# 01_ESP32_MAIN_A.net
KiCad netlist of a schematic drawn in Altium Designer
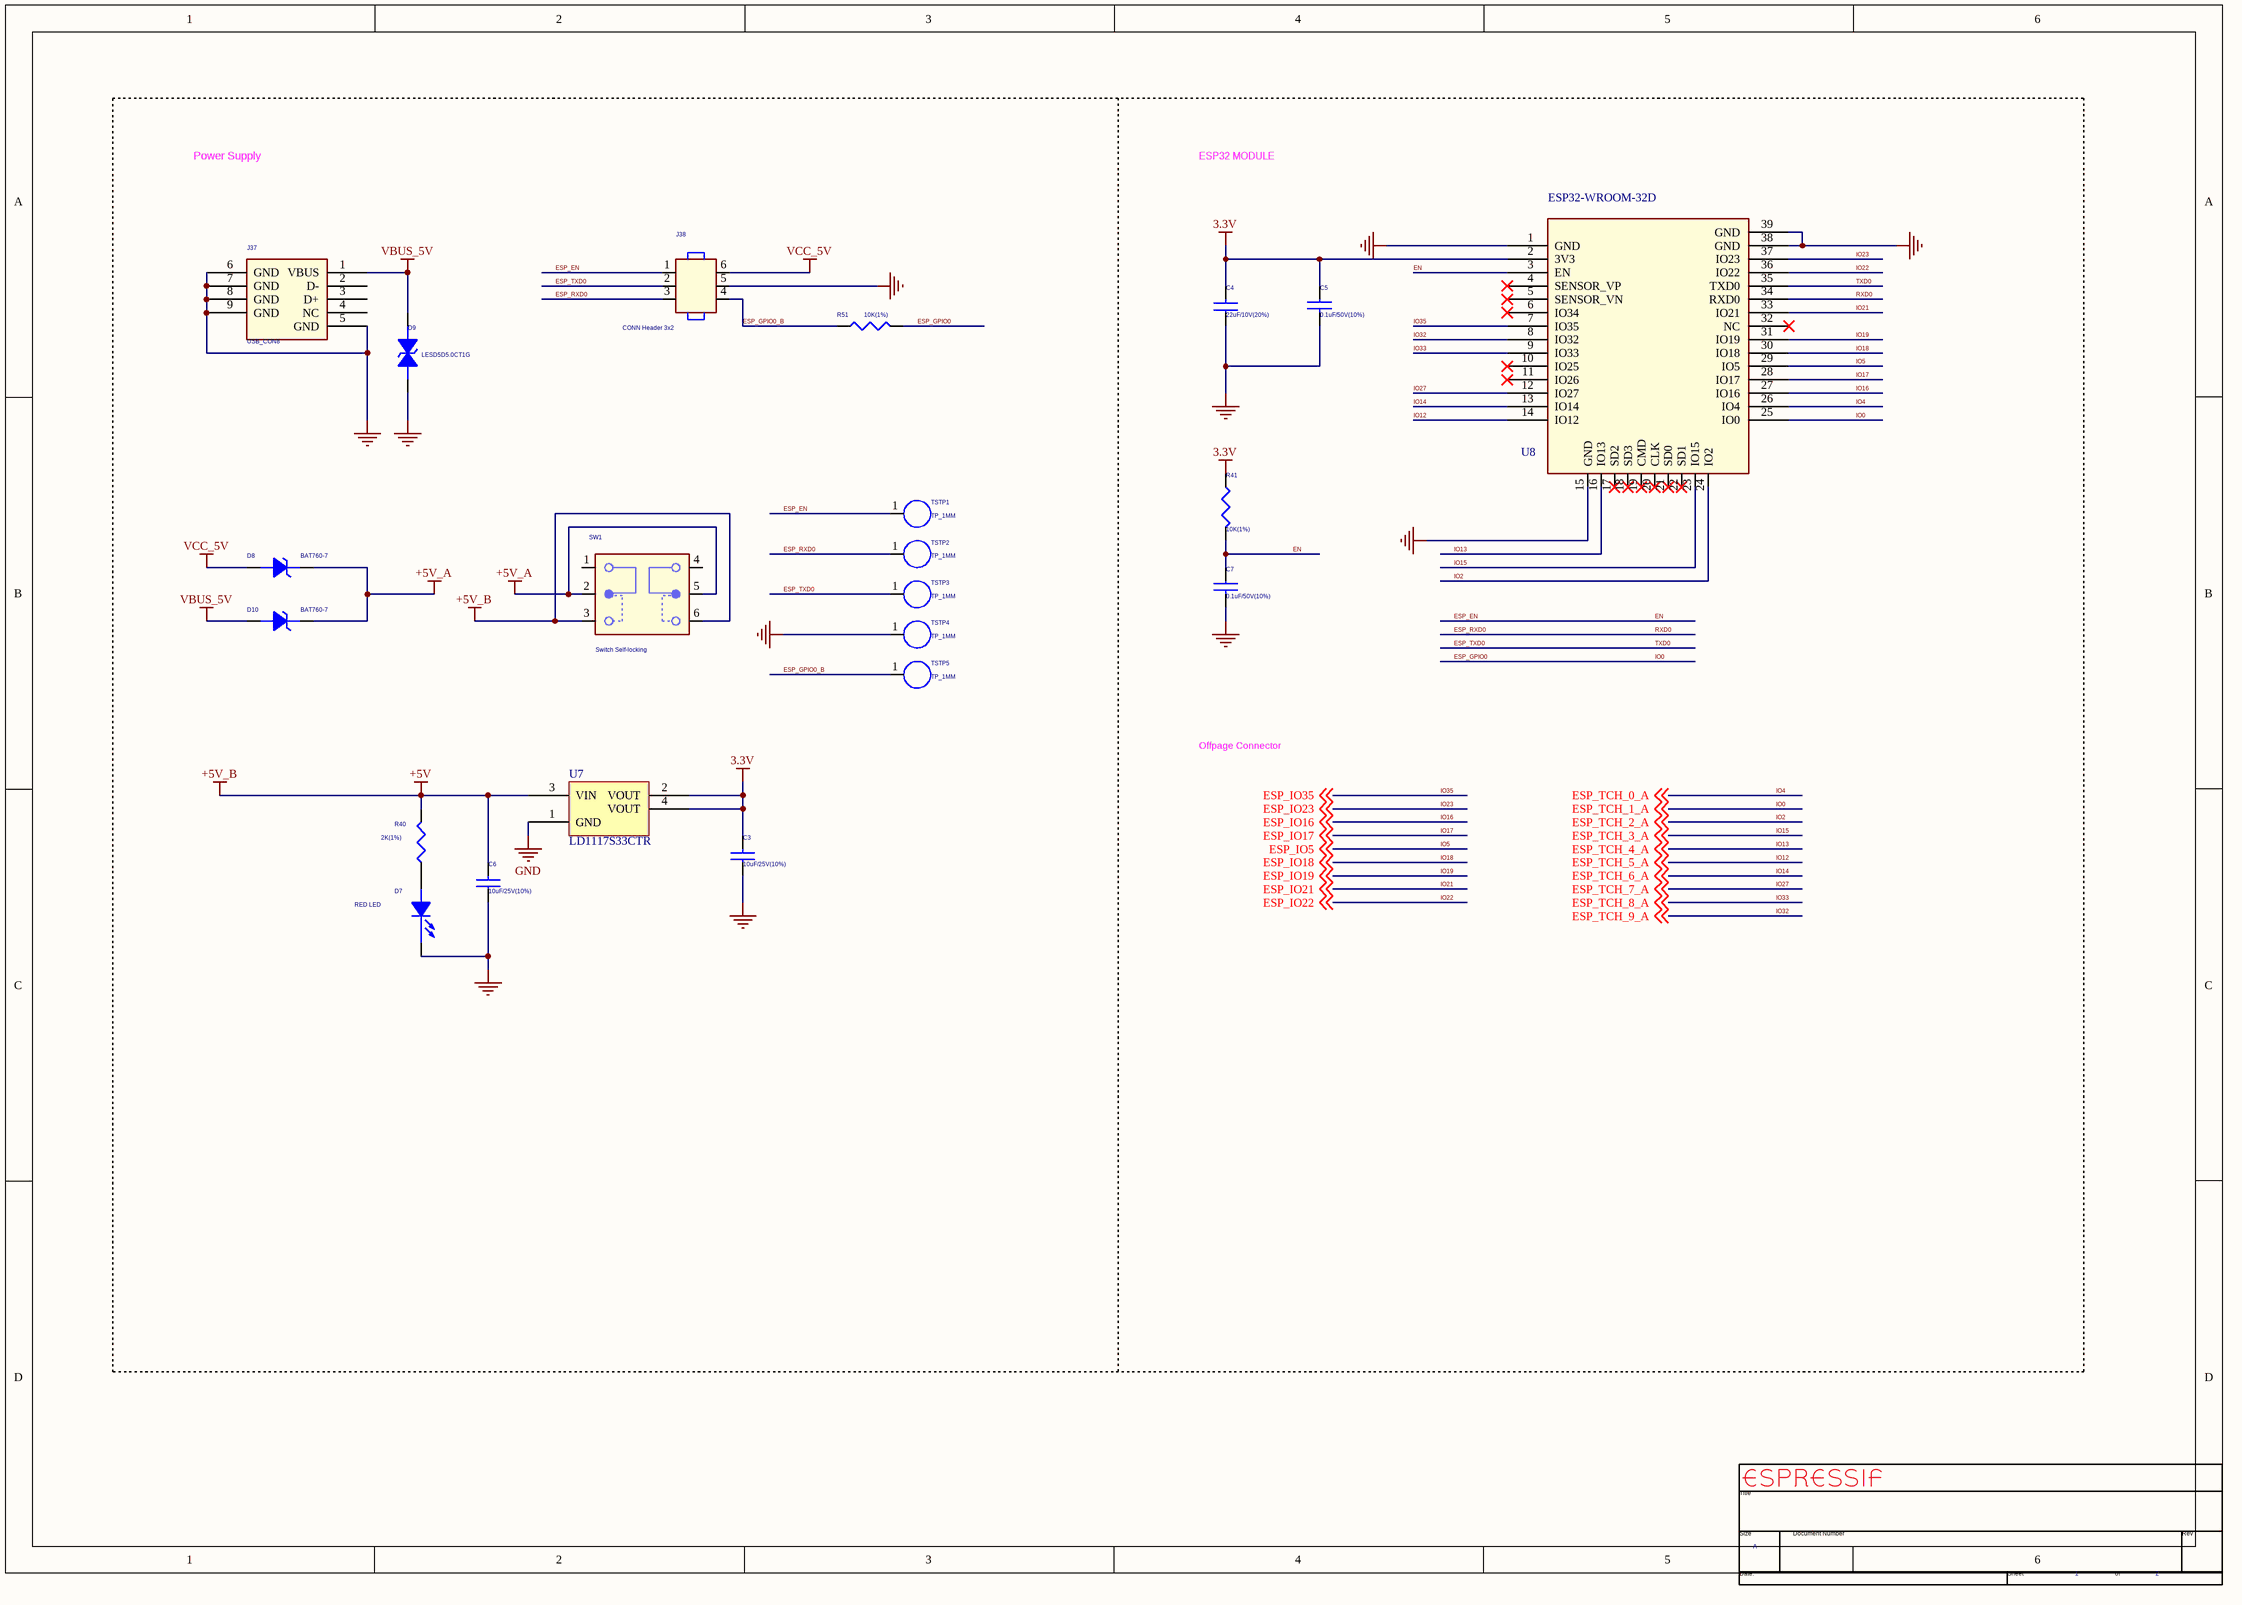
[diagram p0: 01 ESP32 MAIN_A.SchDoc]

(export (version "E")
  (design (tool "Eeschema 10.0.6"))
  (components
    (comp (ref "C3") (value "10uF/25V(10%)") (footprint "0603C") (libsource (lib "*") (part "CAP NP")))
    (comp (ref "C4") (value "22uF/10V(20%)") (footprint "C0603") (libsource (lib "*") (part "CAP NP")))
    (comp (ref "C5") (value "0.1uF/50V(10%)") (footprint "C0402") (libsource (lib "*") (part "CAP NP")))
    (comp (ref "C6") (value "10uF/25V(10%)") (footprint "0603C") (libsource (lib "*") (part "CAP NP")))
    (comp (ref "C7") (value "0.1uF/50V(10%)") (footprint "C0402") (libsource (lib "*") (part "CAP NP")))
    (comp (ref "D7") (value "RED LED") (footprint "0603D/A") (libsource (lib "*") (part "LED_1")))
    (comp (ref "D8") (value "BAT760-7") (footprint "SOD-323") (libsource (lib "*") (part "DIODE_POWER")))
    (comp (ref "D9")
      (value "LESD5D5.0CT1G")
      (footprint "ESD0402")
      (libsource (lib "*") (part "DIODE BI-DIR TRIG"))
    )
    (comp (ref "D10") (value "BAT760-7") (footprint "SOD-323") (libsource (lib "*") (part "DIODE_POWER")))
    (comp (ref "J37") (value "USB_CON8") (footprint "USB_5P") (libsource (lib "*") (part "CON4_2")))
    (comp (ref "J38")
      (value "CONN Header 3x2")
      (footprint "DC3-6P-1P27")
      (libsource (lib "*") (part "12 HEADER_9"))
    )
    (comp (ref "R40") (value "2K(1%)") (footprint "0402R") (libsource (lib "*") (part "RESISTOR_0")))
    (comp (ref "R41") (value "10K(1%)") (footprint "0402R") (libsource (lib "*") (part "RESISTOR_0")))
    (comp (ref "R51") (value "10K(1%)") (footprint "0402R") (libsource (lib "*") (part "RESISTOR_0")))
    (comp (ref "SW1")
      (value "Switch Self-locking")
      (footprint "SW5858-6")
      (libsource (lib "*") (part "Switch_selflocking_6p"))
    )
    (comp (ref "TSTP1") (value "TP_1MM") (footprint "TP_1MM") (libsource (lib "*") (part "CON1_0")))
    (comp (ref "TSTP2") (value "TP_1MM") (footprint "TP_1MM") (libsource (lib "*") (part "CON1_0")))
    (comp (ref "TSTP3") (value "TP_1MM") (footprint "TP_1MM") (libsource (lib "*") (part "CON1_0")))
    (comp (ref "TSTP4") (value "TP_1MM") (footprint "TP_1MM") (libsource (lib "*") (part "CON1_0")))
    (comp (ref "TSTP5") (value "TP_1MM") (footprint "TP_1MM") (libsource (lib "*") (part "CON1_0")))
    (comp (ref "U7")
      (value "LD1117S33CTR")
      (footprint "ST SOT-223")
      (description "IC REG LDO 3.3V 0.8A SOT223")
      (fields (field (name "MANUFACTURER") "STMicroelectronics"))
      (libsource (lib "Celestial Library Database") (part "ST LD1117"))
    )
    (comp (ref "U8")
      (value "ESP32-WROOM-32D")
      (footprint "*MODULE_ESP32-WROOM-32D")
      (description "IC: SoC; GPIO, I2C, I2S, IR, SD, SDIO, SPI, UART; 2.7Ã·3.6VDC; 20dBm")
      (fields (field (name "MF") "Espressif Systems"))
      (libsource (lib "ESP32-WROOM-32D") (part "ESP32-WROOM-32D"))
    )
  )
  (nets
    (net (code "1") (name "+5V") (class "Default")
      (node (ref "C6") (pin "2") (pinfunction "2_2") (pintype "passive"))
      (node (ref "R40") (pin "1") (pinfunction "1_1") (pintype "passive"))
      (node (ref "SW1") (pin "3") (pinfunction "NO1_3") (pintype "passive"))
      (node (ref "SW1") (pin "6") (pinfunction "NO2_6") (pintype "passive"))
      (node (ref "U7") (pin "3") (pinfunction "VIN_3") (pintype "passive"))
    )
    (net (code "2") (name "+5V_A") (class "Default")
      (node (ref "D10") (pin "1") (pinfunction "1_1") (pintype "passive"))
      (node (ref "D8") (pin "1") (pinfunction "1_1") (pintype "passive"))
      (node (ref "SW1") (pin "2") (pinfunction "COM1_2") (pintype "passive"))
      (node (ref "SW1") (pin "5") (pinfunction "COM2_5") (pintype "passive"))
    )
    (net (code "3") (name "/EN") (class "Default")
      (node (ref "C7") (pin "1") (pinfunction "1_1") (pintype "passive"))
      (node (ref "J38") (pin "1") (pinfunction "1_1") (pintype "passive"))
      (node (ref "R41") (pin "2") (pinfunction "2_2") (pintype "passive"))
      (node (ref "TSTP1") (pin "1") (pinfunction "1_1") (pintype "passive"))
      (node (ref "U8") (pin "3") (pinfunction "EN_3") (pintype "passive"))
    )
    (net (code "4") (name "/ESP_GPIO0_B") (class "Default")
      (node (ref "J38") (pin "4") (pinfunction "4_4") (pintype "passive"))
      (node (ref "R51") (pin "1") (pinfunction "1_1") (pintype "passive"))
      (node (ref "TSTP5") (pin "1") (pinfunction "1_1") (pintype "passive"))
    )
    (net (code "5") (name "/ESP_RXD0") (class "Default")
      (node (ref "J38") (pin "3") (pinfunction "3_3") (pintype "passive"))
      (node (ref "TSTP2") (pin "1") (pinfunction "1_1") (pintype "passive"))
      (node (ref "U8") (pin "34") (pinfunction "RXD0_34") (pintype "passive"))
    )
    (net (code "6") (name "/ESP_TXD0") (class "Default")
      (node (ref "J38") (pin "2") (pinfunction "2_2") (pintype "passive"))
      (node (ref "TSTP3") (pin "1") (pinfunction "1_1") (pintype "passive"))
      (node (ref "U8") (pin "35") (pinfunction "TXD0_35") (pintype "passive"))
    )
    (net (code "7") (name "3.3V") (class "Default")
      (node (ref "C3") (pin "2") (pinfunction "2_2") (pintype "passive"))
      (node (ref "C4") (pin "2") (pinfunction "2_2") (pintype "passive"))
      (node (ref "C5") (pin "1") (pinfunction "1_1") (pintype "passive"))
      (node (ref "R41") (pin "1") (pinfunction "1_1") (pintype "passive"))
      (node (ref "U7") (pin "2") (pinfunction "VOUT_2") (pintype "passive"))
      (node (ref "U7") (pin "4") (pinfunction "VOUT_4") (pintype "passive"))
      (node (ref "U8") (pin "2") (pinfunction "3V3_2") (pintype "power_in"))
    )
    (net (code "8") (name "ESP_IO5") (class "Default")
      (node (ref "U8") (pin "29") (pinfunction "IO5_29") (pintype "passive"))
    )
    (net (code "9") (name "ESP_IO16") (class "Default")
      (node (ref "U8") (pin "27") (pinfunction "IO16_27") (pintype "passive"))
    )
    (net (code "10") (name "ESP_IO17") (class "Default")
      (node (ref "U8") (pin "28") (pinfunction "IO17_28") (pintype "passive"))
    )
    (net (code "11") (name "ESP_IO18") (class "Default")
      (node (ref "U8") (pin "30") (pinfunction "IO18_30") (pintype "passive"))
    )
    (net (code "12") (name "ESP_IO19") (class "Default")
      (node (ref "U8") (pin "31") (pinfunction "IO19_31") (pintype "passive"))
    )
    (net (code "13") (name "ESP_IO21") (class "Default")
      (node (ref "U8") (pin "33") (pinfunction "IO21_33") (pintype "passive"))
    )
    (net (code "14") (name "ESP_IO22") (class "Default")
      (node (ref "U8") (pin "36") (pinfunction "IO22_36") (pintype "passive"))
    )
    (net (code "15") (name "ESP_IO23") (class "Default")
      (node (ref "U8") (pin "37") (pinfunction "IO23_37") (pintype "passive"))
    )
    (net (code "16") (name "ESP_IO35") (class "Default")
      (node (ref "U8") (pin "7") (pinfunction "IO35_7") (pintype "passive"))
    )
    (net (code "17") (name "ESP_TCH_0_A") (class "Default")
      (node (ref "U8") (pin "26") (pinfunction "IO4_26") (pintype "passive"))
    )
    (net (code "18") (name "ESP_TCH_1_A") (class "Default")
      (node (ref "R51") (pin "2") (pinfunction "2_2") (pintype "passive"))
      (node (ref "U8") (pin "25") (pinfunction "IO0_25") (pintype "passive"))
    )
    (net (code "19") (name "ESP_TCH_2_A") (class "Default")
      (node (ref "U8") (pin "24") (pinfunction "IO2_24") (pintype "passive"))
    )
    (net (code "20") (name "ESP_TCH_3_A") (class "Default")
      (node (ref "U8") (pin "23") (pinfunction "IO15_23") (pintype "passive"))
    )
    (net (code "21") (name "ESP_TCH_4_A") (class "Default")
      (node (ref "U8") (pin "16") (pinfunction "IO13_16") (pintype "passive"))
    )
    (net (code "22") (name "ESP_TCH_5_A") (class "Default")
      (node (ref "U8") (pin "14") (pinfunction "IO12_14") (pintype "passive"))
    )
    (net (code "23") (name "ESP_TCH_6_A") (class "Default")
      (node (ref "U8") (pin "13") (pinfunction "IO14_13") (pintype "passive"))
    )
    (net (code "24") (name "ESP_TCH_7_A") (class "Default")
      (node (ref "U8") (pin "12") (pinfunction "IO27_12") (pintype "passive"))
    )
    (net (code "25") (name "ESP_TCH_8_A") (class "Default")
      (node (ref "U8") (pin "9") (pinfunction "IO33_9") (pintype "passive"))
    )
    (net (code "26") (name "ESP_TCH_9_A") (class "Default")
      (node (ref "U8") (pin "8") (pinfunction "IO32_8") (pintype "passive"))
    )
    (net (code "27") (name "GND") (class "Default")
      (node (ref "C3") (pin "1") (pinfunction "1_1") (pintype "passive"))
      (node (ref "C4") (pin "1") (pinfunction "1_1") (pintype "passive"))
      (node (ref "C5") (pin "2") (pinfunction "2_2") (pintype "passive"))
      (node (ref "C6") (pin "1") (pinfunction "1_1") (pintype "passive"))
      (node (ref "C7") (pin "2") (pinfunction "2_2") (pintype "passive"))
      (node (ref "D7") (pin "2") (pinfunction "CATHODE_2") (pintype "passive"))
      (node (ref "D9") (pin "2") (pinfunction "2_2") (pintype "passive"))
      (node (ref "J37") (pin "5") (pinfunction "GND_5") (pintype "power_in"))
      (node (ref "J37") (pin "6") (pinfunction "GND_6") (pintype "power_in"))
      (node (ref "J37") (pin "7") (pinfunction "GND_7") (pintype "power_in"))
      (node (ref "J37") (pin "8") (pinfunction "GND_8") (pintype "power_in"))
      (node (ref "J37") (pin "9") (pinfunction "GND_9") (pintype "power_in"))
      (node (ref "J38") (pin "5") (pinfunction "5_5") (pintype "passive"))
      (node (ref "TSTP4") (pin "1") (pinfunction "1_1") (pintype "passive"))
      (node (ref "U7") (pin "1") (pinfunction "GND_1") (pintype "passive"))
      (node (ref "U8") (pin "1") (pinfunction "GND_1") (pintype "power_in"))
      (node (ref "U8") (pin "15") (pinfunction "GND_15") (pintype "power_in"))
      (node (ref "U8") (pin "38") (pinfunction "GND_38") (pintype "passive"))
      (node (ref "U8") (pin "39") (pinfunction "GND_39") (pintype "power_in"))
    )
    (net (code "28") (name "Net-(D7-ANODE)") (class "Default")
      (node (ref "D7") (pin "1") (pinfunction "ANODE_1") (pintype "passive"))
      (node (ref "R40") (pin "2") (pinfunction "2_2") (pintype "passive"))
    )
    (net (code "29") (name "VBUS_5V") (class "Default")
      (node (ref "D10") (pin "2") (pinfunction "2_2") (pintype "passive"))
      (node (ref "D9") (pin "1") (pinfunction "1_1") (pintype "passive"))
      (node (ref "J37") (pin "1") (pinfunction "VBUS_1") (pintype "power_in"))
    )
    (net (code "30") (name "VCC_5V") (class "Default")
      (node (ref "D8") (pin "2") (pinfunction "2_2") (pintype "passive"))
      (node (ref "J38") (pin "6") (pinfunction "6_6") (pintype "passive"))
    )
    (net (code "31") (name "unconnected-(J37-D+-Pad3)") (class "Default")
      (node (ref "J37") (pin "3") (pinfunction "D+_3") (pintype "passive"))
    )
    (net (code "32") (name "unconnected-(J37-D--Pad2)") (class "Default")
      (node (ref "J37") (pin "2") (pinfunction "D-_2") (pintype "passive"))
    )
    (net (code "33") (name "unconnected-(J37-NC-Pad4)") (class "Default")
      (node (ref "J37") (pin "4") (pinfunction "NC_4") (pintype "passive"))
    )
    (net (code "34") (name "unconnected-(SW1-NC1-Pad1)") (class "Default")
      (node (ref "SW1") (pin "1") (pinfunction "NC1_1") (pintype "passive"))
    )
    (net (code "35") (name "unconnected-(SW1-NC2-Pad4)") (class "Default")
      (node (ref "SW1") (pin "4") (pinfunction "NC2_4") (pintype "passive"))
    )
    (net (code "36") (name "unconnected-(U8-CLK-Pad20)") (class "Default")
      (node (ref "U8") (pin "20") (pinfunction "CLK_20") (pintype "passive+no_connect"))
    )
    (net (code "37") (name "unconnected-(U8-CMD-Pad19)") (class "Default")
      (node (ref "U8") (pin "19") (pinfunction "CMD_19") (pintype "passive+no_connect"))
    )
    (net (code "38") (name "unconnected-(U8-IO25-Pad10)") (class "Default")
      (node (ref "U8") (pin "10") (pinfunction "IO25_10") (pintype "passive+no_connect"))
    )
    (net (code "39") (name "unconnected-(U8-IO26-Pad11)") (class "Default")
      (node (ref "U8") (pin "11") (pinfunction "IO26_11") (pintype "passive+no_connect"))
    )
    (net (code "40") (name "unconnected-(U8-IO34-Pad6)") (class "Default")
      (node (ref "U8") (pin "6") (pinfunction "IO34_6") (pintype "passive+no_connect"))
    )
    (net (code "41") (name "unconnected-(U8-NC-Pad32)") (class "Default")
      (node (ref "U8") (pin "32") (pinfunction "NC_32") (pintype "passive+no_connect"))
    )
    (net (code "42") (name "unconnected-(U8-SD0-Pad21)") (class "Default")
      (node (ref "U8") (pin "21") (pinfunction "SD0_21") (pintype "passive+no_connect"))
    )
    (net (code "43") (name "unconnected-(U8-SD1-Pad22)") (class "Default")
      (node (ref "U8") (pin "22") (pinfunction "SD1_22") (pintype "passive+no_connect"))
    )
    (net (code "44") (name "unconnected-(U8-SD2-Pad17)") (class "Default")
      (node (ref "U8") (pin "17") (pinfunction "SD2_17") (pintype "passive+no_connect"))
    )
    (net (code "45") (name "unconnected-(U8-SD3-Pad18)") (class "Default")
      (node (ref "U8") (pin "18") (pinfunction "SD3_18") (pintype "passive+no_connect"))
    )
    (net (code "46") (name "unconnected-(U8-SENSOR_VN-Pad5)") (class "Default")
      (node (ref "U8") (pin "5") (pinfunction "SENSOR_VN_5") (pintype "passive+no_connect"))
    )
    (net (code "47") (name "unconnected-(U8-SENSOR_VP-Pad4)") (class "Default")
      (node (ref "U8") (pin "4") (pinfunction "SENSOR_VP_4") (pintype "passive+no_connect"))
    )
  )
)
